# Si4707-Breakout.net
KiCad netlist of a schematic drawn in EAGLE
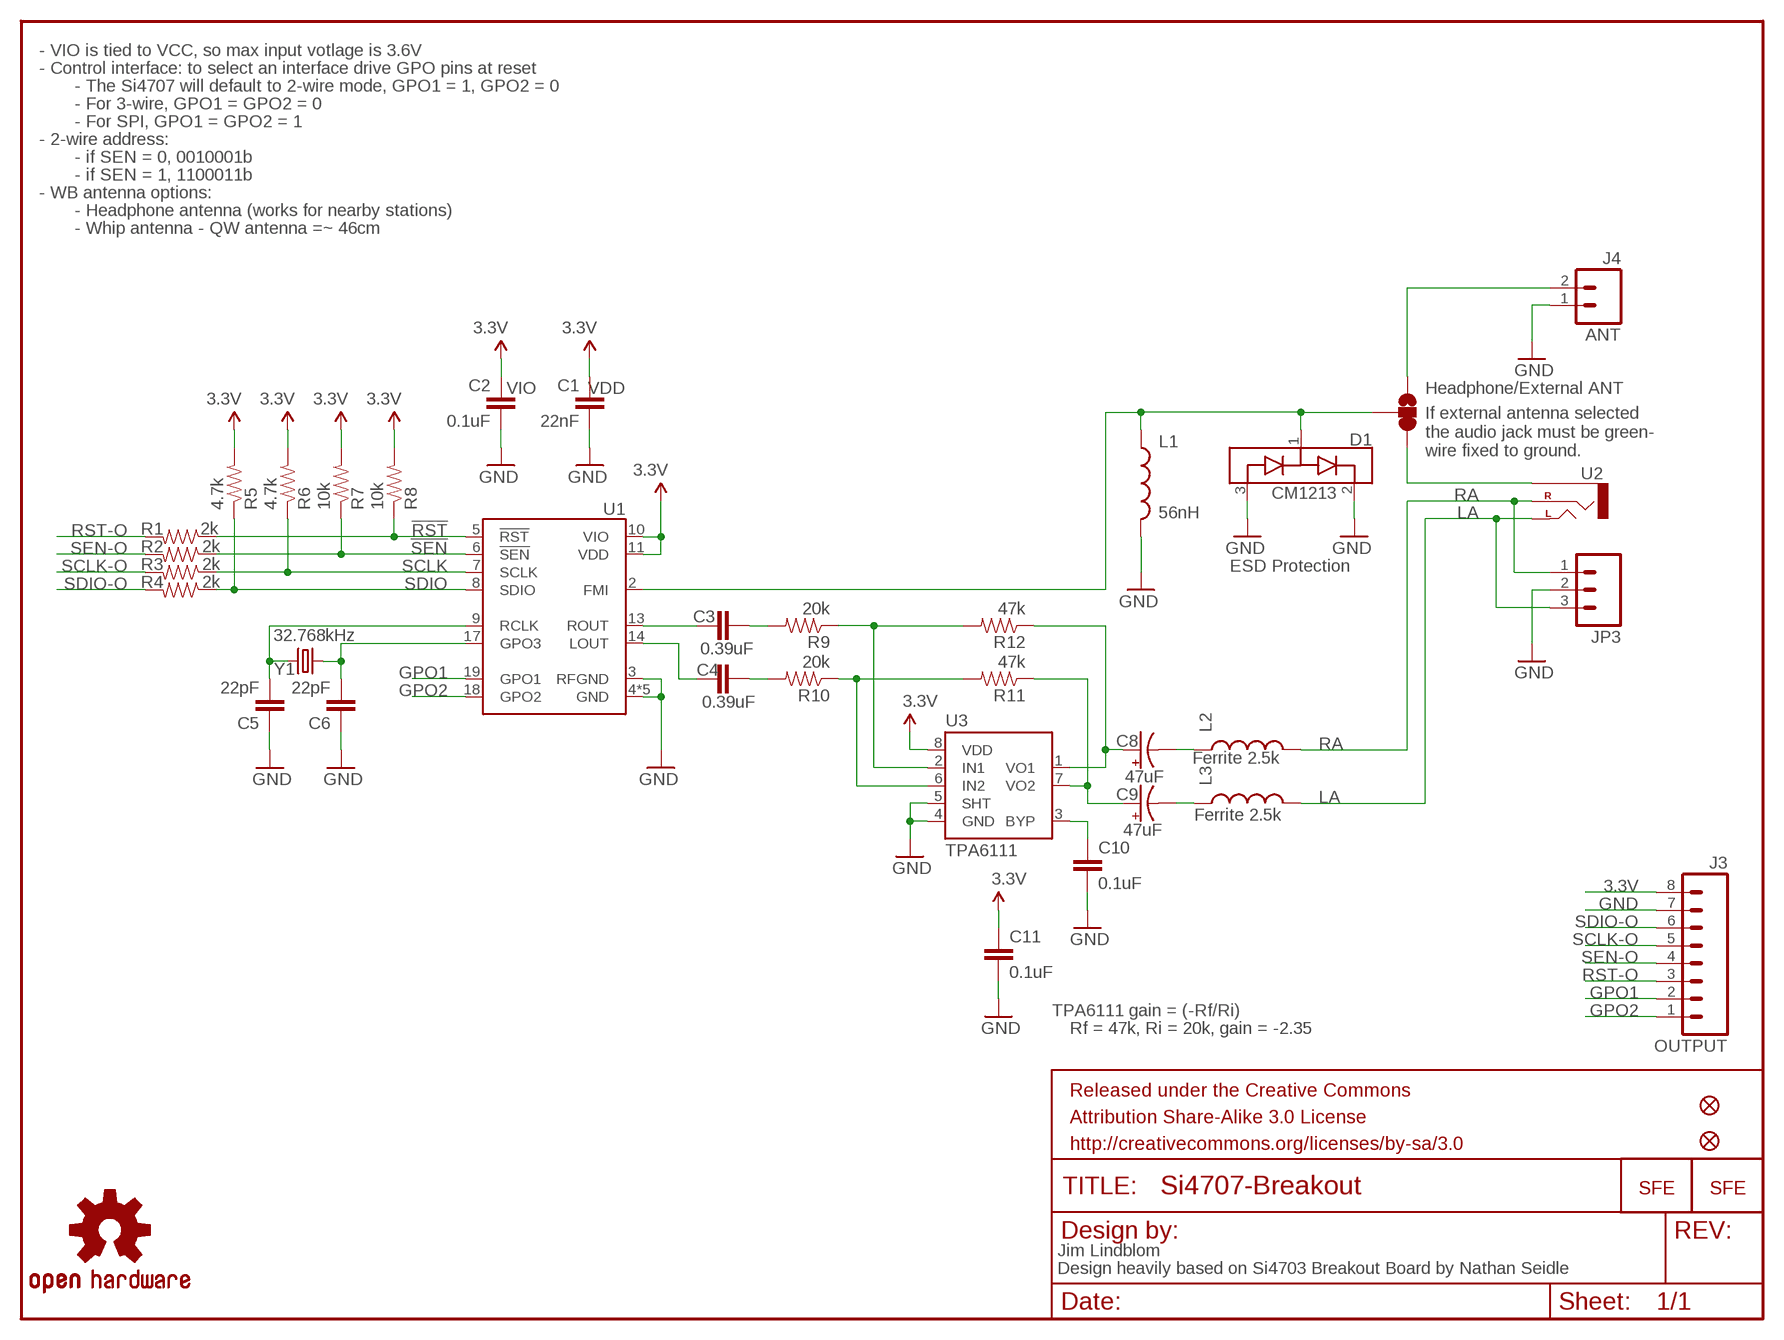
[diagram p0: schematic, sheet 1]

(export (version "E")
  (design (tool "Eeschema 10.0.6"))
  (components
    (comp (ref "C1")
      (value "22nF")
      (footprint "eagle-import:0402-CAP")
      (libsource (lib "eagle-import") (part "CAP0402-CAP"))
    )
    (comp (ref "C2")
      (value "0.1uF")
      (footprint "eagle-import:0402-CAP")
      (libsource (lib "eagle-import") (part "CAP0402-CAP"))
    )
    (comp (ref "C3")
      (value "0.39uF")
      (footprint "eagle-import:0402-CAP")
      (libsource (lib "eagle-import") (part "CAP0402-CAP"))
    )
    (comp (ref "C4")
      (value "0.39uF")
      (footprint "eagle-import:0402-CAP")
      (libsource (lib "eagle-import") (part "CAP0402-CAP"))
    )
    (comp (ref "C5")
      (value "22pF")
      (footprint "eagle-import:0402-CAP")
      (libsource (lib "eagle-import") (part "CAP0402-CAP"))
    )
    (comp (ref "C6")
      (value "22pF")
      (footprint "eagle-import:0402-CAP")
      (libsource (lib "eagle-import") (part "CAP0402-CAP"))
    )
    (comp (ref "C8")
      (value "47uF")
      (footprint "eagle-import:EIA3528")
      (libsource (lib "eagle-import") (part "CAP_POL3528"))
    )
    (comp (ref "C9")
      (value "47uF")
      (footprint "eagle-import:EIA3528")
      (libsource (lib "eagle-import") (part "CAP_POL3528"))
    )
    (comp (ref "C10")
      (value "0.1uF")
      (footprint "eagle-import:0402-CAP")
      (libsource (lib "eagle-import") (part "CAP0402-CAP"))
    )
    (comp (ref "C11")
      (value "0.1uF")
      (footprint "eagle-import:0402-CAP")
      (libsource (lib "eagle-import") (part "CAP0402-CAP"))
    )
    (comp (ref "D1")
      (value "CM1213")
      (footprint "eagle-import:SOT23-3")
      (libsource (lib "eagle-import") (part "CM1213"))
    )
    (comp (ref "FRAME1")
      (value "FRAME-LETTER")
      (footprint "eagle-import:CREATIVE_COMMONS")
      (libsource (lib "eagle-import") (part "FRAME-LETTER"))
    )
    (comp (ref "J3")
      (value "OUTPUT")
      (footprint "eagle-import:1X08")
      (libsource (lib "eagle-import") (part "M081X08"))
    )
    (comp (ref "J4")
      (value "ANT")
      (footprint "eagle-import:1X02")
      (libsource (lib "eagle-import") (part "M02PTH"))
    )
    (comp (ref "JP1")
      (value "LOGO-SFENEW")
      (footprint "eagle-import:SFE-NEW-WEBLOGO")
      (libsource (lib "eagle-import") (part "LOGO-SFENEW"))
    )
    (comp (ref "JP2")
      (value "LOGO-SFESK")
      (footprint "eagle-import:SFE-LOGO-FLAME")
      (libsource (lib "eagle-import") (part "LOGO-SFESK"))
    )
    (comp (ref "JP3")
      (value "M03PTH")
      (footprint "eagle-import:1X03")
      (libsource (lib "eagle-import") (part "M03PTH"))
    )
    (comp (ref "JP4")
      (value "FIDUCIALUFIDUCIAL")
      (footprint "eagle-import:MICRO-FIDUCIAL")
      (libsource (lib "eagle-import") (part "FIDUCIALUFIDUCIAL"))
    )
    (comp (ref "JP5")
      (value "FIDUCIALUFIDUCIAL")
      (footprint "eagle-import:MICRO-FIDUCIAL")
      (libsource (lib "eagle-import") (part "FIDUCIALUFIDUCIAL"))
    )
    (comp (ref "L1")
      (value "56nH")
      (footprint "eagle-import:0603")
      (libsource (lib "eagle-import") (part "INDUCTOR0603"))
    )
    (comp (ref "L2")
      (value "Ferrite 2.5k")
      (footprint "eagle-import:C0402")
      (libsource (lib "eagle-import") (part "INDUCTOR0402"))
    )
    (comp (ref "L3")
      (value "Ferrite 2.5k")
      (footprint "eagle-import:C0402")
      (libsource (lib "eagle-import") (part "INDUCTOR0402"))
    )
    (comp (ref "R1")
      (value "2k")
      (footprint "eagle-import:0402-RES")
      (libsource (lib "eagle-import") (part "RESISTOR0402-RES"))
    )
    (comp (ref "R2")
      (value "2k")
      (footprint "eagle-import:0402-RES")
      (libsource (lib "eagle-import") (part "RESISTOR0402-RES"))
    )
    (comp (ref "R3")
      (value "2k")
      (footprint "eagle-import:0402-RES")
      (libsource (lib "eagle-import") (part "RESISTOR0402-RES"))
    )
    (comp (ref "R4")
      (value "2k")
      (footprint "eagle-import:0402-RES")
      (libsource (lib "eagle-import") (part "RESISTOR0402-RES"))
    )
    (comp (ref "R5")
      (value "4.7k")
      (footprint "eagle-import:0402-RES")
      (libsource (lib "eagle-import") (part "RESISTOR0402-RES"))
    )
    (comp (ref "R6")
      (value "4.7k")
      (footprint "eagle-import:0402-RES")
      (libsource (lib "eagle-import") (part "RESISTOR0402-RES"))
    )
    (comp (ref "R7")
      (value "10k")
      (footprint "eagle-import:0402-RES")
      (libsource (lib "eagle-import") (part "RESISTOR0402-RES"))
    )
    (comp (ref "R8")
      (value "10k")
      (footprint "eagle-import:0402-RES")
      (libsource (lib "eagle-import") (part "RESISTOR0402-RES"))
    )
    (comp (ref "R9")
      (value "20k")
      (footprint "eagle-import:0402-RES")
      (libsource (lib "eagle-import") (part "RESISTOR0402-RES"))
    )
    (comp (ref "R10")
      (value "20k")
      (footprint "eagle-import:0402-RES")
      (libsource (lib "eagle-import") (part "RESISTOR0402-RES"))
    )
    (comp (ref "R11")
      (value "47k")
      (footprint "eagle-import:0402-RES")
      (libsource (lib "eagle-import") (part "RESISTOR0402-RES"))
    )
    (comp (ref "R12")
      (value "47k")
      (footprint "eagle-import:0402-RES")
      (libsource (lib "eagle-import") (part "RESISTOR0402-RES"))
    )
    (comp (ref "SJ2")
      (value "SOLDERJUMPER_2WAYS")
      (footprint "eagle-import:SJ_3")
      (libsource (lib "eagle-import") (part "SOLDERJUMPER_2WAYS"))
    )
    (comp (ref "U$2")
      (value "OSHW-LOGOS")
      (footprint "eagle-import:OSHW-LOGO-S")
      (libsource (lib "eagle-import") (part "OSHW-LOGOS"))
    )
    (comp (ref "U1")
      (value "SI4707")
      (footprint "eagle-import:SI470X")
      (libsource (lib "eagle-import") (part "SI4707"))
    )
    (comp (ref "U2")
      (value "AUDIO-JACKSMD2")
      (footprint "eagle-import:AUDIO-JACK-3.5MM-SMD")
      (libsource (lib "eagle-import") (part "AUDIO-JACKSMD2"))
    )
    (comp (ref "U3")
      (value "TPA6111")
      (footprint "eagle-import:SPARKFUN_SO08")
      (libsource (lib "eagle-import") (part "SPARKFUN_TPA6111SMD"))
    )
    (comp (ref "Y1")
      (value "32.768kHz")
      (footprint "eagle-import:CRYSTAL-32KHZ-SMD")
      (libsource (lib "eagle-import") (part "CRYSTAL32-SMD"))
    )
  )
  (nets
    (net (code "1") (name "/GPO1") (class "Default")
      (node (ref "J3") (pin "2") (pinfunction "2_2") (pintype "passive"))
      (node (ref "U1") (pin "19") (pinfunction "GPO1_19") (pintype "bidirectional"))
    )
    (net (code "2") (name "/GPO2") (class "Default")
      (node (ref "J3") (pin "1") (pinfunction "1_1") (pintype "passive"))
      (node (ref "U1") (pin "18") (pinfunction "GPO2_18") (pintype "bidirectional"))
    )
    (net (code "3") (name "/LA") (class "Default")
      (node (ref "JP3") (pin "3") (pinfunction "3_3") (pintype "passive"))
      (node (ref "L3") (pin "2") (pinfunction "2_2") (pintype "passive"))
      (node (ref "U2") (pin "TIP") (pinfunction "LEFT_TIP") (pintype "bidirectional"))
    )
    (net (code "4") (name "/RA") (class "Default")
      (node (ref "JP3") (pin "1") (pinfunction "1_1") (pintype "passive"))
      (node (ref "L2") (pin "2") (pinfunction "2_2") (pintype "passive"))
      (node (ref "U2") (pin "RING") (pinfunction "RIGHT_RING") (pintype "bidirectional"))
    )
    (net (code "5") (name "/RST-O") (class "Default")
      (node (ref "J3") (pin "3") (pinfunction "3_3") (pintype "passive"))
      (node (ref "R1") (pin "2") (pinfunction "2_2") (pintype "passive"))
    )
    (net (code "6") (name "/SCLK") (class "Default")
      (node (ref "R3") (pin "1") (pinfunction "1_1") (pintype "passive"))
      (node (ref "R6") (pin "1") (pinfunction "1_1") (pintype "passive"))
      (node (ref "U1") (pin "7") (pinfunction "SCLK_7") (pintype "bidirectional"))
    )
    (net (code "7") (name "/SCLK-O") (class "Default")
      (node (ref "J3") (pin "5") (pinfunction "5_5") (pintype "passive"))
      (node (ref "R3") (pin "2") (pinfunction "2_2") (pintype "passive"))
    )
    (net (code "8") (name "/SDIO") (class "Default")
      (node (ref "R4") (pin "1") (pinfunction "1_1") (pintype "passive"))
      (node (ref "R5") (pin "1") (pinfunction "1_1") (pintype "passive"))
      (node (ref "U1") (pin "8") (pinfunction "SDIO_8") (pintype "bidirectional"))
    )
    (net (code "9") (name "/SDIO-O") (class "Default")
      (node (ref "J3") (pin "6") (pinfunction "6_6") (pintype "passive"))
      (node (ref "R4") (pin "2") (pinfunction "2_2") (pintype "passive"))
    )
    (net (code "10") (name "/SEN-O") (class "Default")
      (node (ref "J3") (pin "4") (pinfunction "4_4") (pintype "passive"))
      (node (ref "R2") (pin "2") (pinfunction "2_2") (pintype "passive"))
    )
    (net (code "11") (name "/~{RST}") (class "Default")
      (node (ref "R1") (pin "1") (pinfunction "1_1") (pintype "passive"))
      (node (ref "R8") (pin "1") (pinfunction "1_1") (pintype "passive"))
      (node (ref "U1") (pin "5") (pinfunction "~{RST}_5") (pintype "bidirectional"))
    )
    (net (code "12") (name "/~{SEN}") (class "Default")
      (node (ref "R2") (pin "1") (pinfunction "1_1") (pintype "passive"))
      (node (ref "R7") (pin "1") (pinfunction "1_1") (pintype "passive"))
      (node (ref "U1") (pin "6") (pinfunction "~{SEN}_6") (pintype "bidirectional"))
    )
    (net (code "13") (name "3.3V") (class "Default")
      (node (ref "C1") (pin "1") (pinfunction "1_1") (pintype "passive"))
      (node (ref "C11") (pin "1") (pinfunction "1_1") (pintype "passive"))
      (node (ref "C2") (pin "1") (pinfunction "1_1") (pintype "passive"))
      (node (ref "J3") (pin "8") (pinfunction "8_8") (pintype "passive"))
      (node (ref "R5") (pin "2") (pinfunction "2_2") (pintype "passive"))
      (node (ref "R6") (pin "2") (pinfunction "2_2") (pintype "passive"))
      (node (ref "R7") (pin "2") (pinfunction "2_2") (pintype "passive"))
      (node (ref "R8") (pin "2") (pinfunction "2_2") (pintype "passive"))
      (node (ref "U1") (pin "10") (pinfunction "VIO_10") (pintype "bidirectional"))
      (node (ref "U1") (pin "11") (pinfunction "VDD_11") (pintype "bidirectional"))
      (node (ref "U3") (pin "8") (pinfunction "VDD_8") (pintype "bidirectional"))
    )
    (net (code "14") (name "GND") (class "Default")
      (node (ref "C1") (pin "2") (pinfunction "2_2") (pintype "passive"))
      (node (ref "C10") (pin "2") (pinfunction "2_2") (pintype "passive"))
      (node (ref "C11") (pin "2") (pinfunction "2_2") (pintype "passive"))
      (node (ref "C2") (pin "2") (pinfunction "2_2") (pintype "passive"))
      (node (ref "C5") (pin "1") (pinfunction "1_1") (pintype "passive"))
      (node (ref "C6") (pin "1") (pinfunction "1_1") (pintype "passive"))
      (node (ref "D1") (pin "2") (pinfunction "VP_2") (pintype "bidirectional"))
      (node (ref "D1") (pin "3") (pinfunction "VN_3") (pintype "bidirectional"))
      (node (ref "J3") (pin "7") (pinfunction "7_7") (pintype "passive"))
      (node (ref "J4") (pin "1") (pinfunction "1_1") (pintype "passive"))
      (node (ref "JP3") (pin "2") (pinfunction "2_2") (pintype "passive"))
      (node (ref "L1") (pin "2") (pinfunction "2_2") (pintype "passive"))
      (node (ref "U1") (pin "12") (pinfunction "GND_12") (pintype "bidirectional"))
      (node (ref "U1") (pin "15") (pinfunction "GND_15") (pintype "bidirectional"))
      (node (ref "U1") (pin "16") (pinfunction "GND_16") (pintype "bidirectional"))
      (node (ref "U1") (pin "21") (pinfunction "GND_21") (pintype "bidirectional"))
      (node (ref "U1") (pin "3") (pinfunction "RFGND_3") (pintype "bidirectional"))
      (node (ref "U1") (pin "4") (pinfunction "GND_4") (pintype "bidirectional"))
      (node (ref "U3") (pin "4") (pinfunction "GND_4") (pintype "bidirectional"))
      (node (ref "U3") (pin "5") (pinfunction "SHT_5") (pintype "bidirectional"))
    )
    (net (code "15") (name "Net-(C3-Pad2)") (class "Default")
      (node (ref "C3") (pin "2") (pinfunction "2_2") (pintype "passive"))
      (node (ref "R9") (pin "2") (pinfunction "2_2") (pintype "passive"))
    )
    (net (code "16") (name "Net-(C4-Pad2)") (class "Default")
      (node (ref "C4") (pin "2") (pinfunction "2_2") (pintype "passive"))
      (node (ref "R10") (pin "2") (pinfunction "2_2") (pintype "passive"))
    )
    (net (code "17") (name "Net-(C8-+)") (class "Default")
      (node (ref "C8") (pin "A") (pinfunction "+_A") (pintype "passive"))
      (node (ref "R12") (pin "1") (pinfunction "1_1") (pintype "passive"))
      (node (ref "U3") (pin "1") (pinfunction "VO1_1") (pintype "bidirectional"))
    )
    (net (code "18") (name "Net-(C8--)") (class "Default")
      (node (ref "C8") (pin "C") (pinfunction "-_C") (pintype "passive"))
      (node (ref "L2") (pin "1") (pinfunction "1_1") (pintype "passive"))
    )
    (net (code "19") (name "Net-(C9-+)") (class "Default")
      (node (ref "C9") (pin "A") (pinfunction "+_A") (pintype "passive"))
      (node (ref "R11") (pin "1") (pinfunction "1_1") (pintype "passive"))
      (node (ref "U3") (pin "7") (pinfunction "VO2_7") (pintype "bidirectional"))
    )
    (net (code "20") (name "Net-(C9--)") (class "Default")
      (node (ref "C9") (pin "C") (pinfunction "-_C") (pintype "passive"))
      (node (ref "L3") (pin "1") (pinfunction "1_1") (pintype "passive"))
    )
    (net (code "21") (name "Net-(D1-CH1)") (class "Default")
      (node (ref "D1") (pin "1") (pinfunction "CH1_1") (pintype "bidirectional"))
      (node (ref "L1") (pin "1") (pinfunction "1_1") (pintype "passive"))
      (node (ref "SJ2") (pin "2") (pinfunction "2_2") (pintype "passive"))
      (node (ref "U1") (pin "2") (pinfunction "FMI_2") (pintype "bidirectional"))
    )
    (net (code "22") (name "Net-(J4-Pad2)") (class "Default")
      (node (ref "J4") (pin "2") (pinfunction "2_2") (pintype "passive"))
      (node (ref "SJ2") (pin "3") (pinfunction "3_3") (pintype "passive"))
    )
    (net (code "23") (name "Net-(SJ2-Pad1)") (class "Default")
      (node (ref "SJ2") (pin "1") (pinfunction "1_1") (pintype "passive"))
      (node (ref "U2") (pin "SLEEVE") (pinfunction "SLEEVE_SLEEVE") (pintype "bidirectional"))
    )
    (net (code "24") (name "Net-(U1-GPO3)") (class "Default")
      (node (ref "C6") (pin "2") (pinfunction "2_2") (pintype "passive"))
      (node (ref "U1") (pin "17") (pinfunction "GPO3_17") (pintype "bidirectional"))
      (node (ref "Y1") (pin "X1") (pinfunction "1_X1") (pintype "passive"))
    )
    (net (code "25") (name "Net-(U1-LOUT)") (class "Default")
      (node (ref "C4") (pin "1") (pinfunction "1_1") (pintype "passive"))
      (node (ref "U1") (pin "14") (pinfunction "LOUT_14") (pintype "bidirectional"))
    )
    (net (code "26") (name "Net-(U1-RCLK)") (class "Default")
      (node (ref "C5") (pin "2") (pinfunction "2_2") (pintype "passive"))
      (node (ref "U1") (pin "9") (pinfunction "RCLK_9") (pintype "bidirectional"))
      (node (ref "Y1") (pin "X2") (pinfunction "2_X2") (pintype "passive"))
    )
    (net (code "27") (name "Net-(U1-ROUT)") (class "Default")
      (node (ref "C3") (pin "1") (pinfunction "1_1") (pintype "passive"))
      (node (ref "U1") (pin "13") (pinfunction "ROUT_13") (pintype "bidirectional"))
    )
    (net (code "28") (name "Net-(U3-BYP)") (class "Default")
      (node (ref "C10") (pin "1") (pinfunction "1_1") (pintype "passive"))
      (node (ref "U3") (pin "3") (pinfunction "BYP_3") (pintype "bidirectional"))
    )
    (net (code "29") (name "Net-(U3-IN1)") (class "Default")
      (node (ref "R12") (pin "2") (pinfunction "2_2") (pintype "passive"))
      (node (ref "R9") (pin "1") (pinfunction "1_1") (pintype "passive"))
      (node (ref "U3") (pin "2") (pinfunction "IN1_2") (pintype "bidirectional"))
    )
    (net (code "30") (name "Net-(U3-IN2)") (class "Default")
      (node (ref "R10") (pin "1") (pinfunction "1_1") (pintype "passive"))
      (node (ref "R11") (pin "2") (pinfunction "2_2") (pintype "passive"))
      (node (ref "U3") (pin "6") (pinfunction "IN2_6") (pintype "bidirectional"))
    )
  )
)
